# Satyrr_six_loadcell_pcb.net
KiCad netlist of a schematic drawn in EAGLE
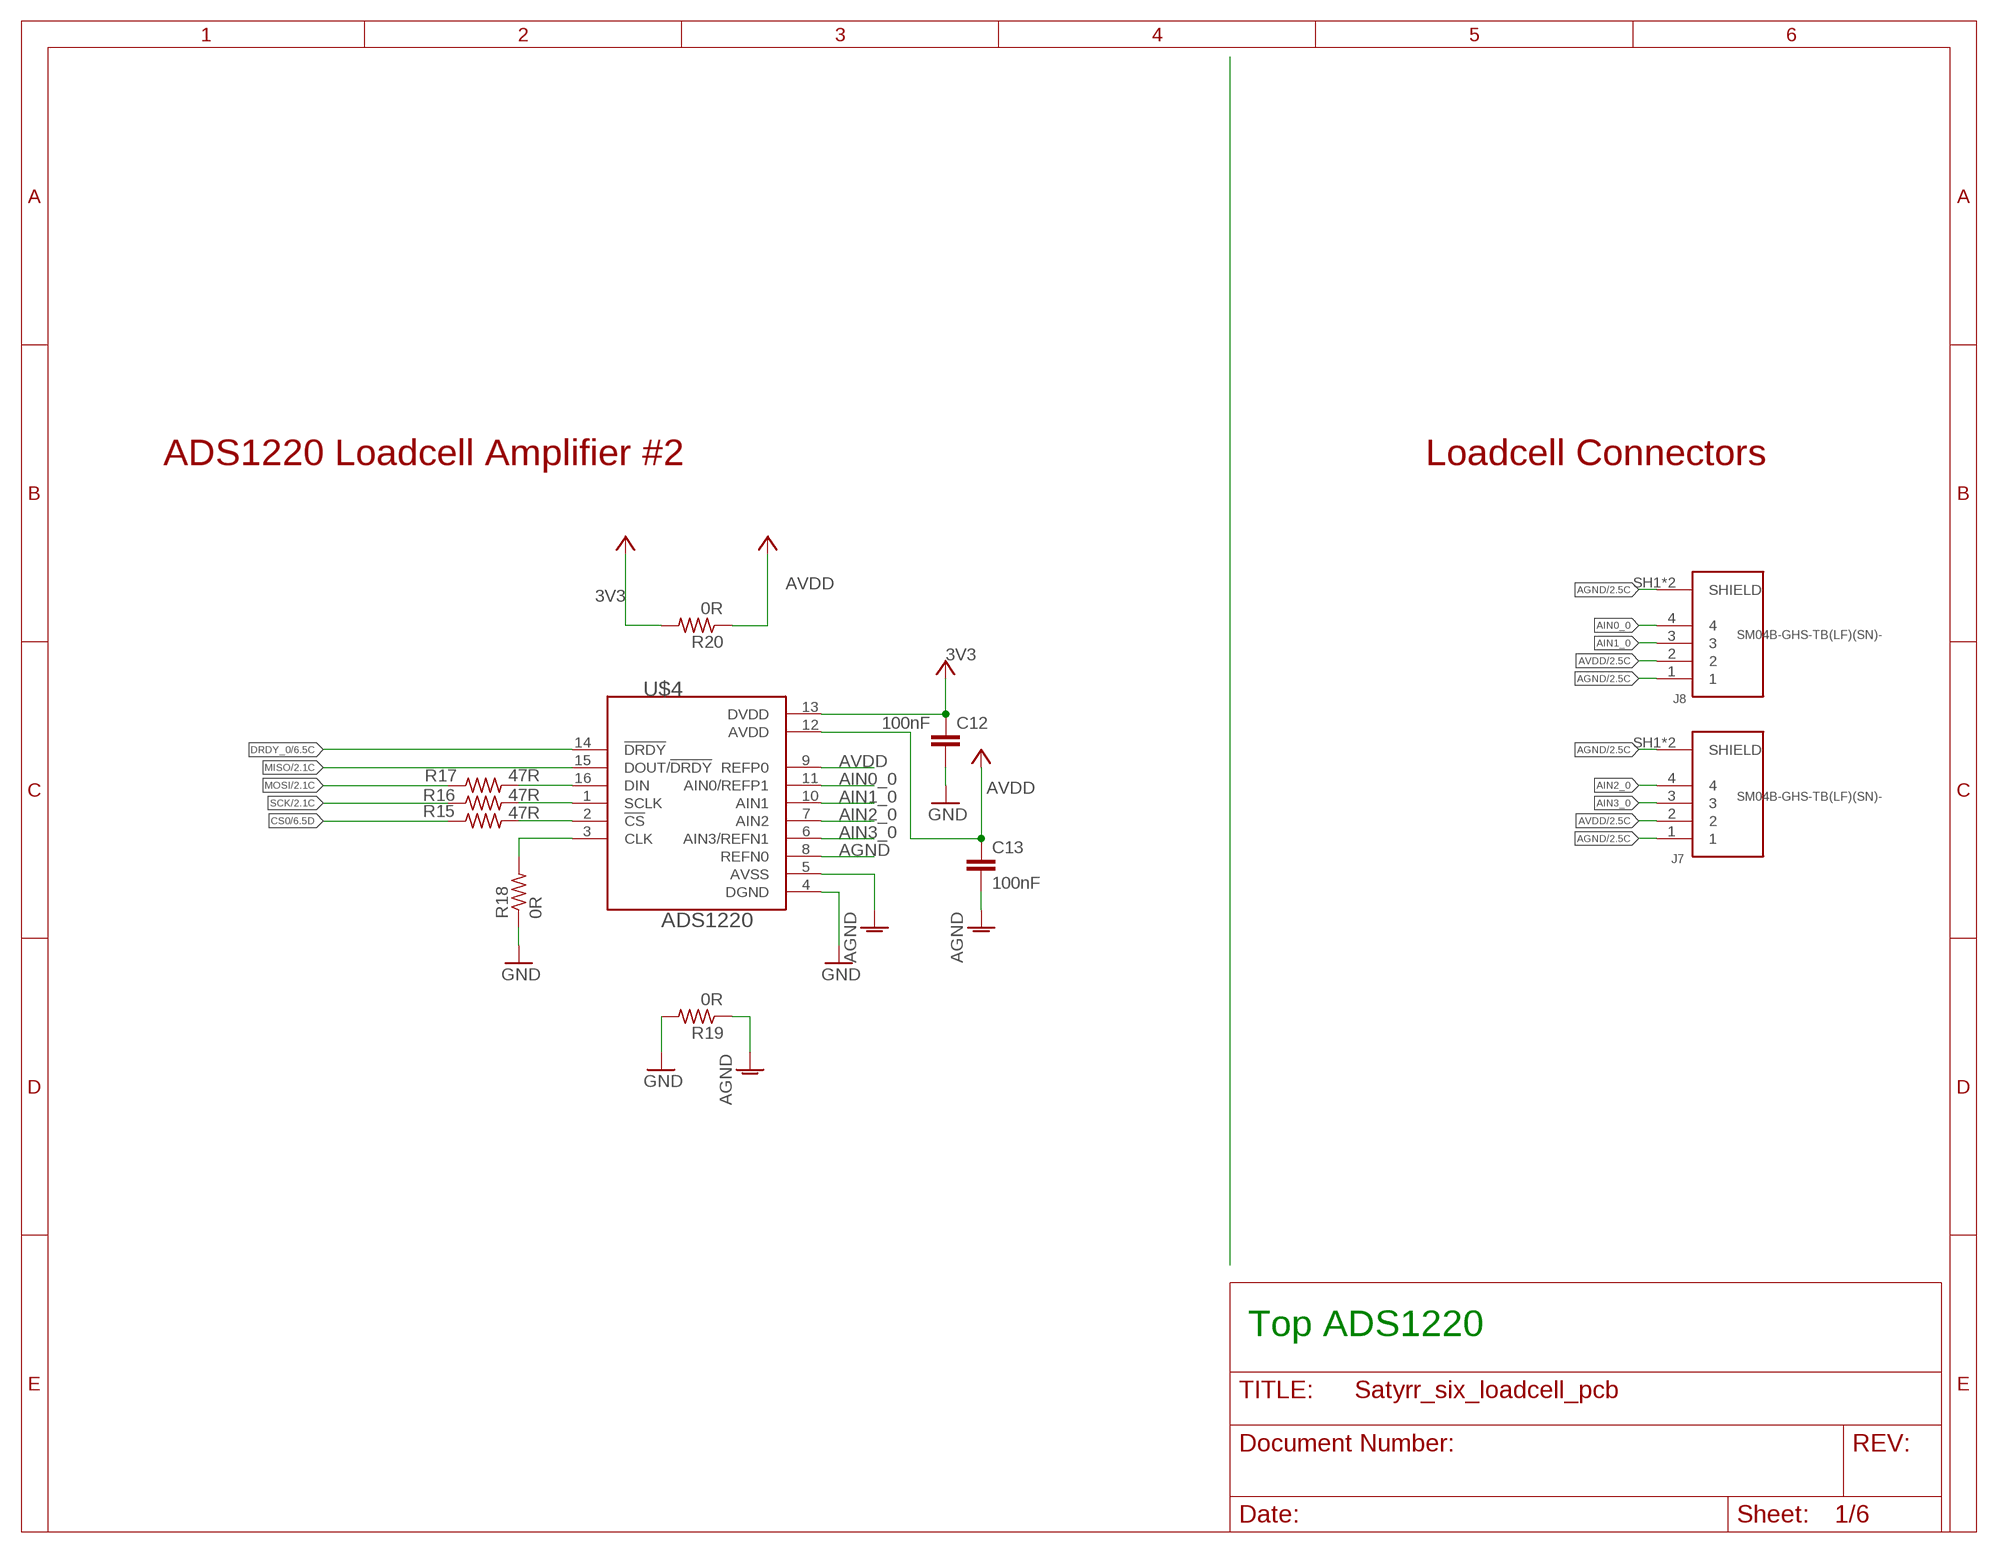
[diagram p0: schematic, sheet 1]
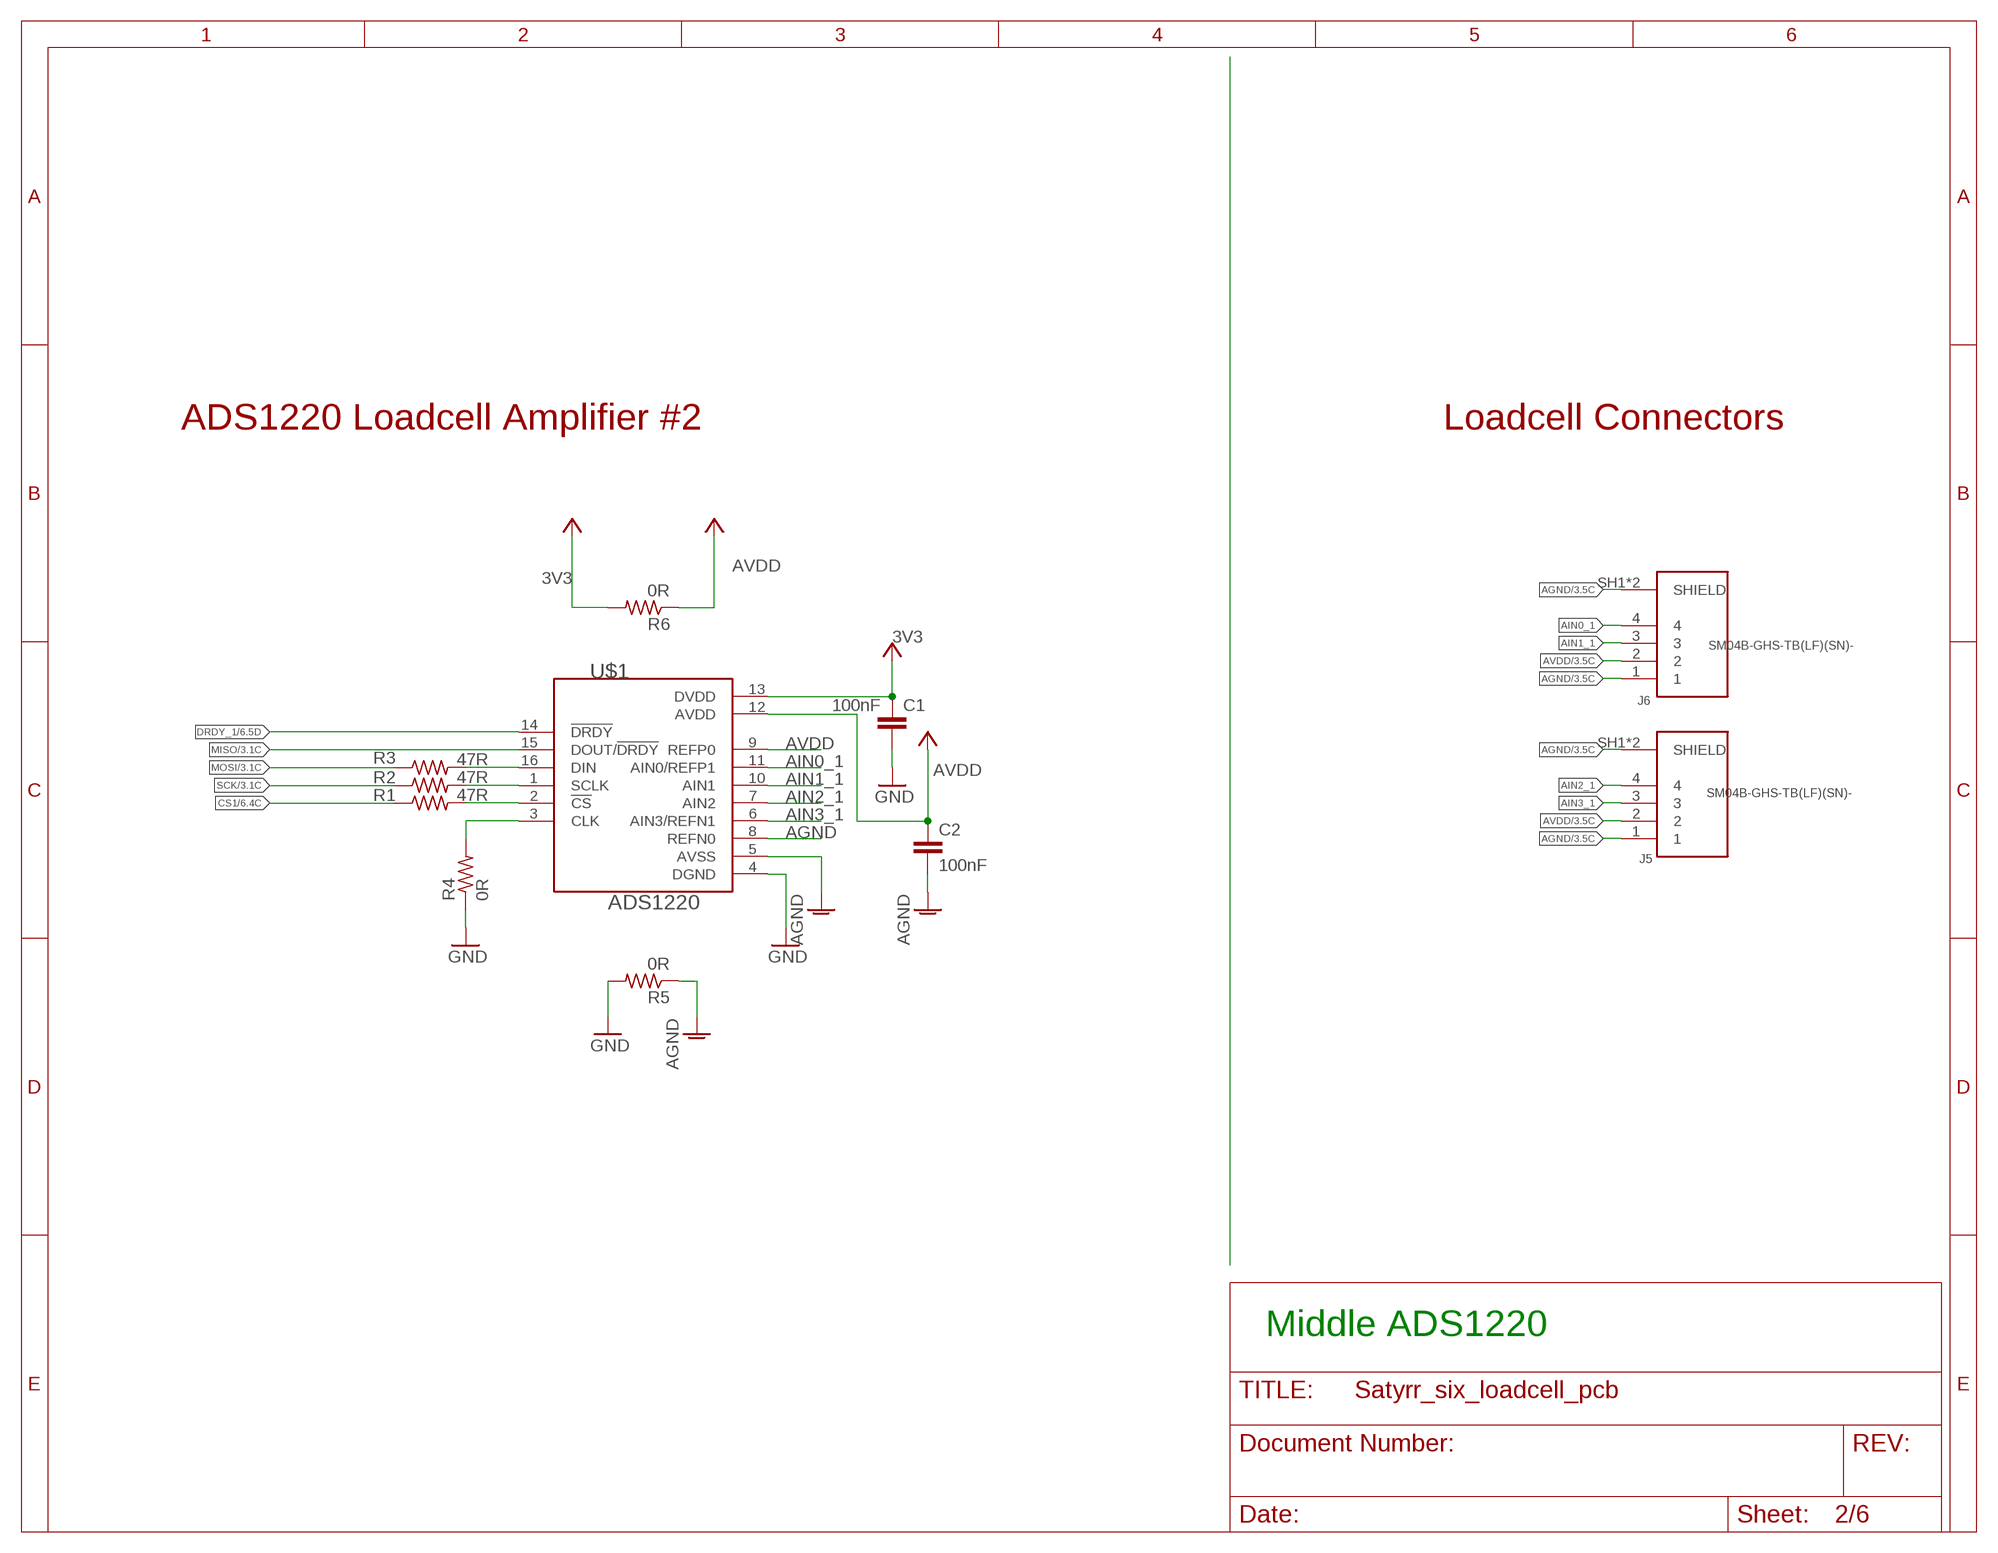
[diagram p1: schematic, sheet 2]
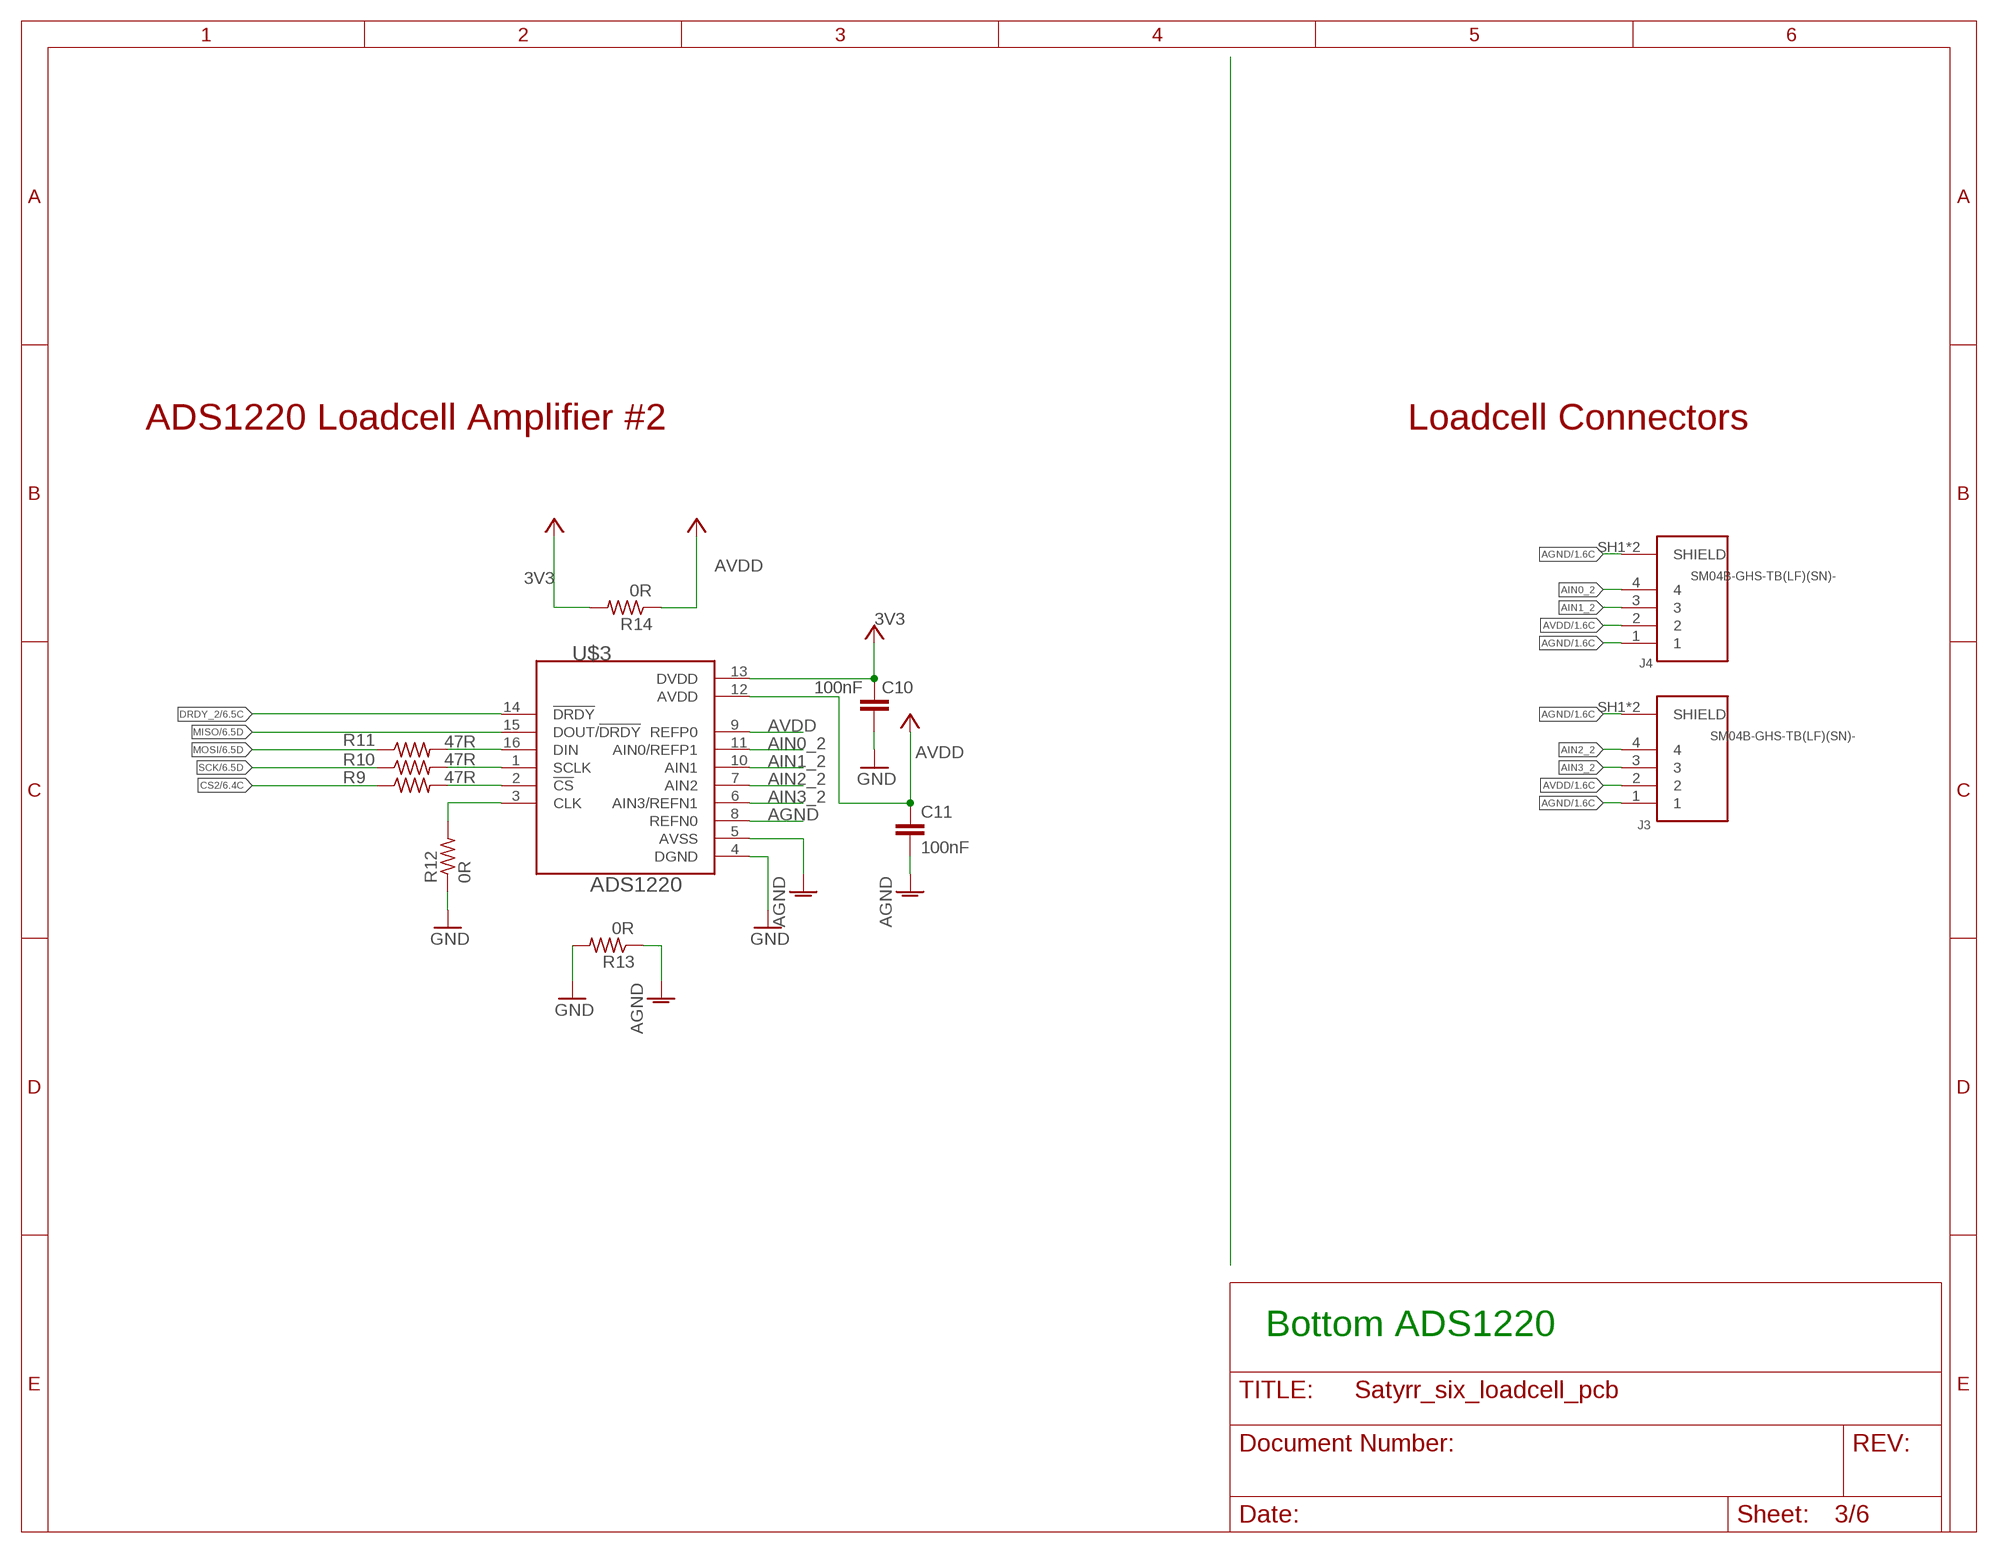
[diagram p2: schematic, sheet 3]
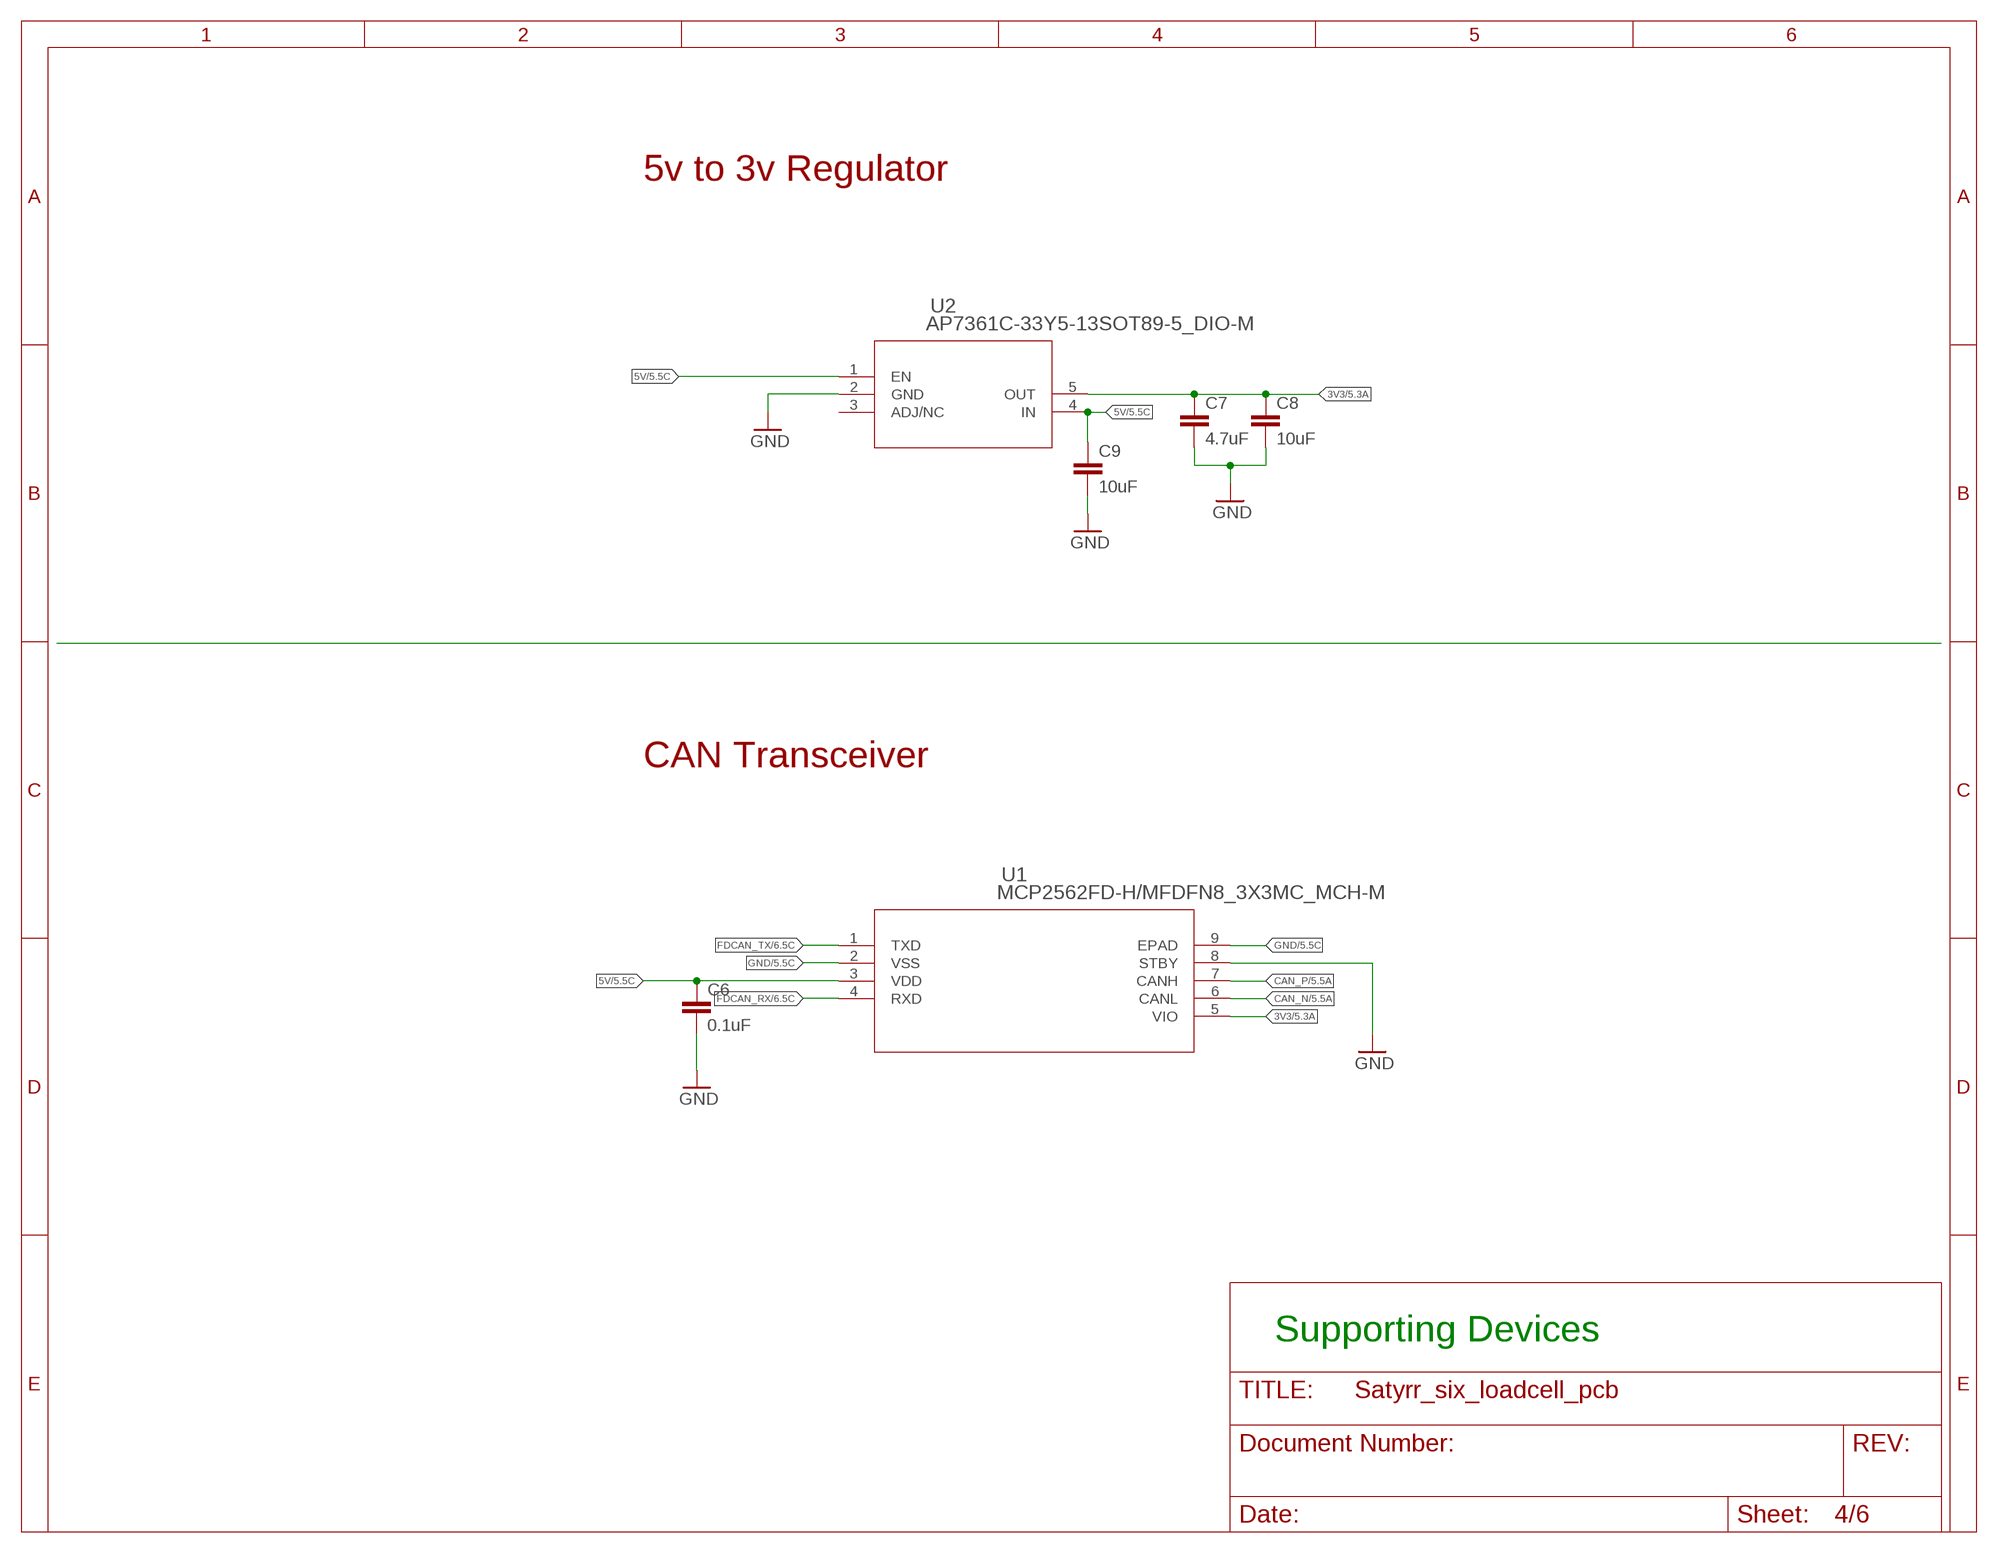
[diagram p3: schematic, sheet 4]
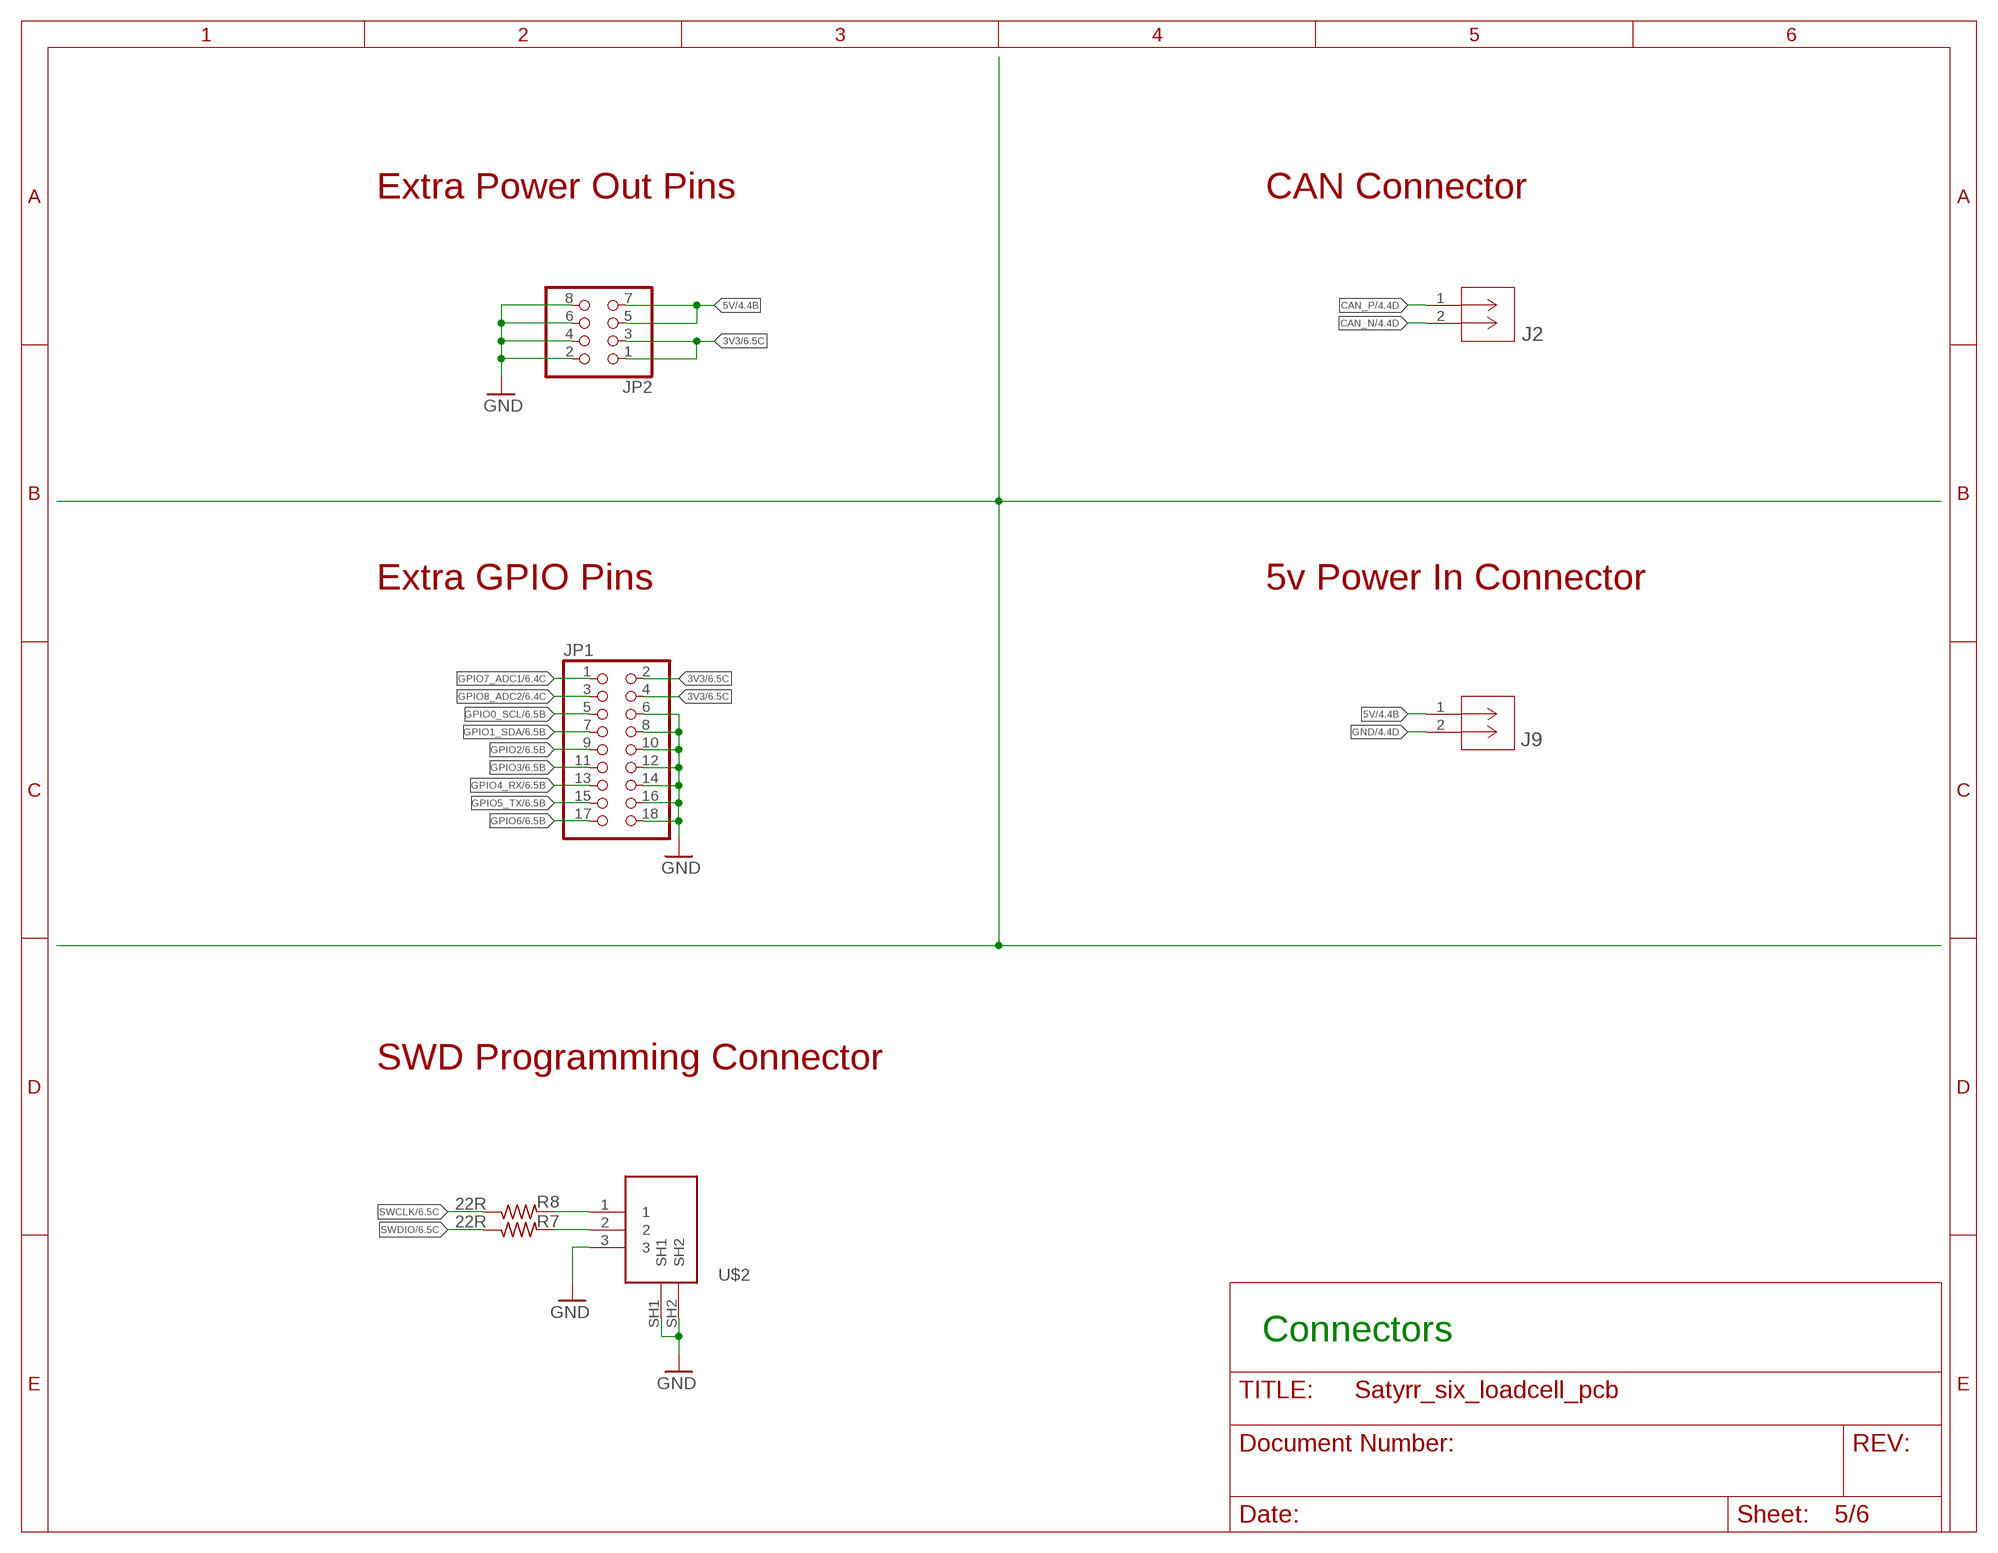
[diagram p4: schematic, sheet 5]
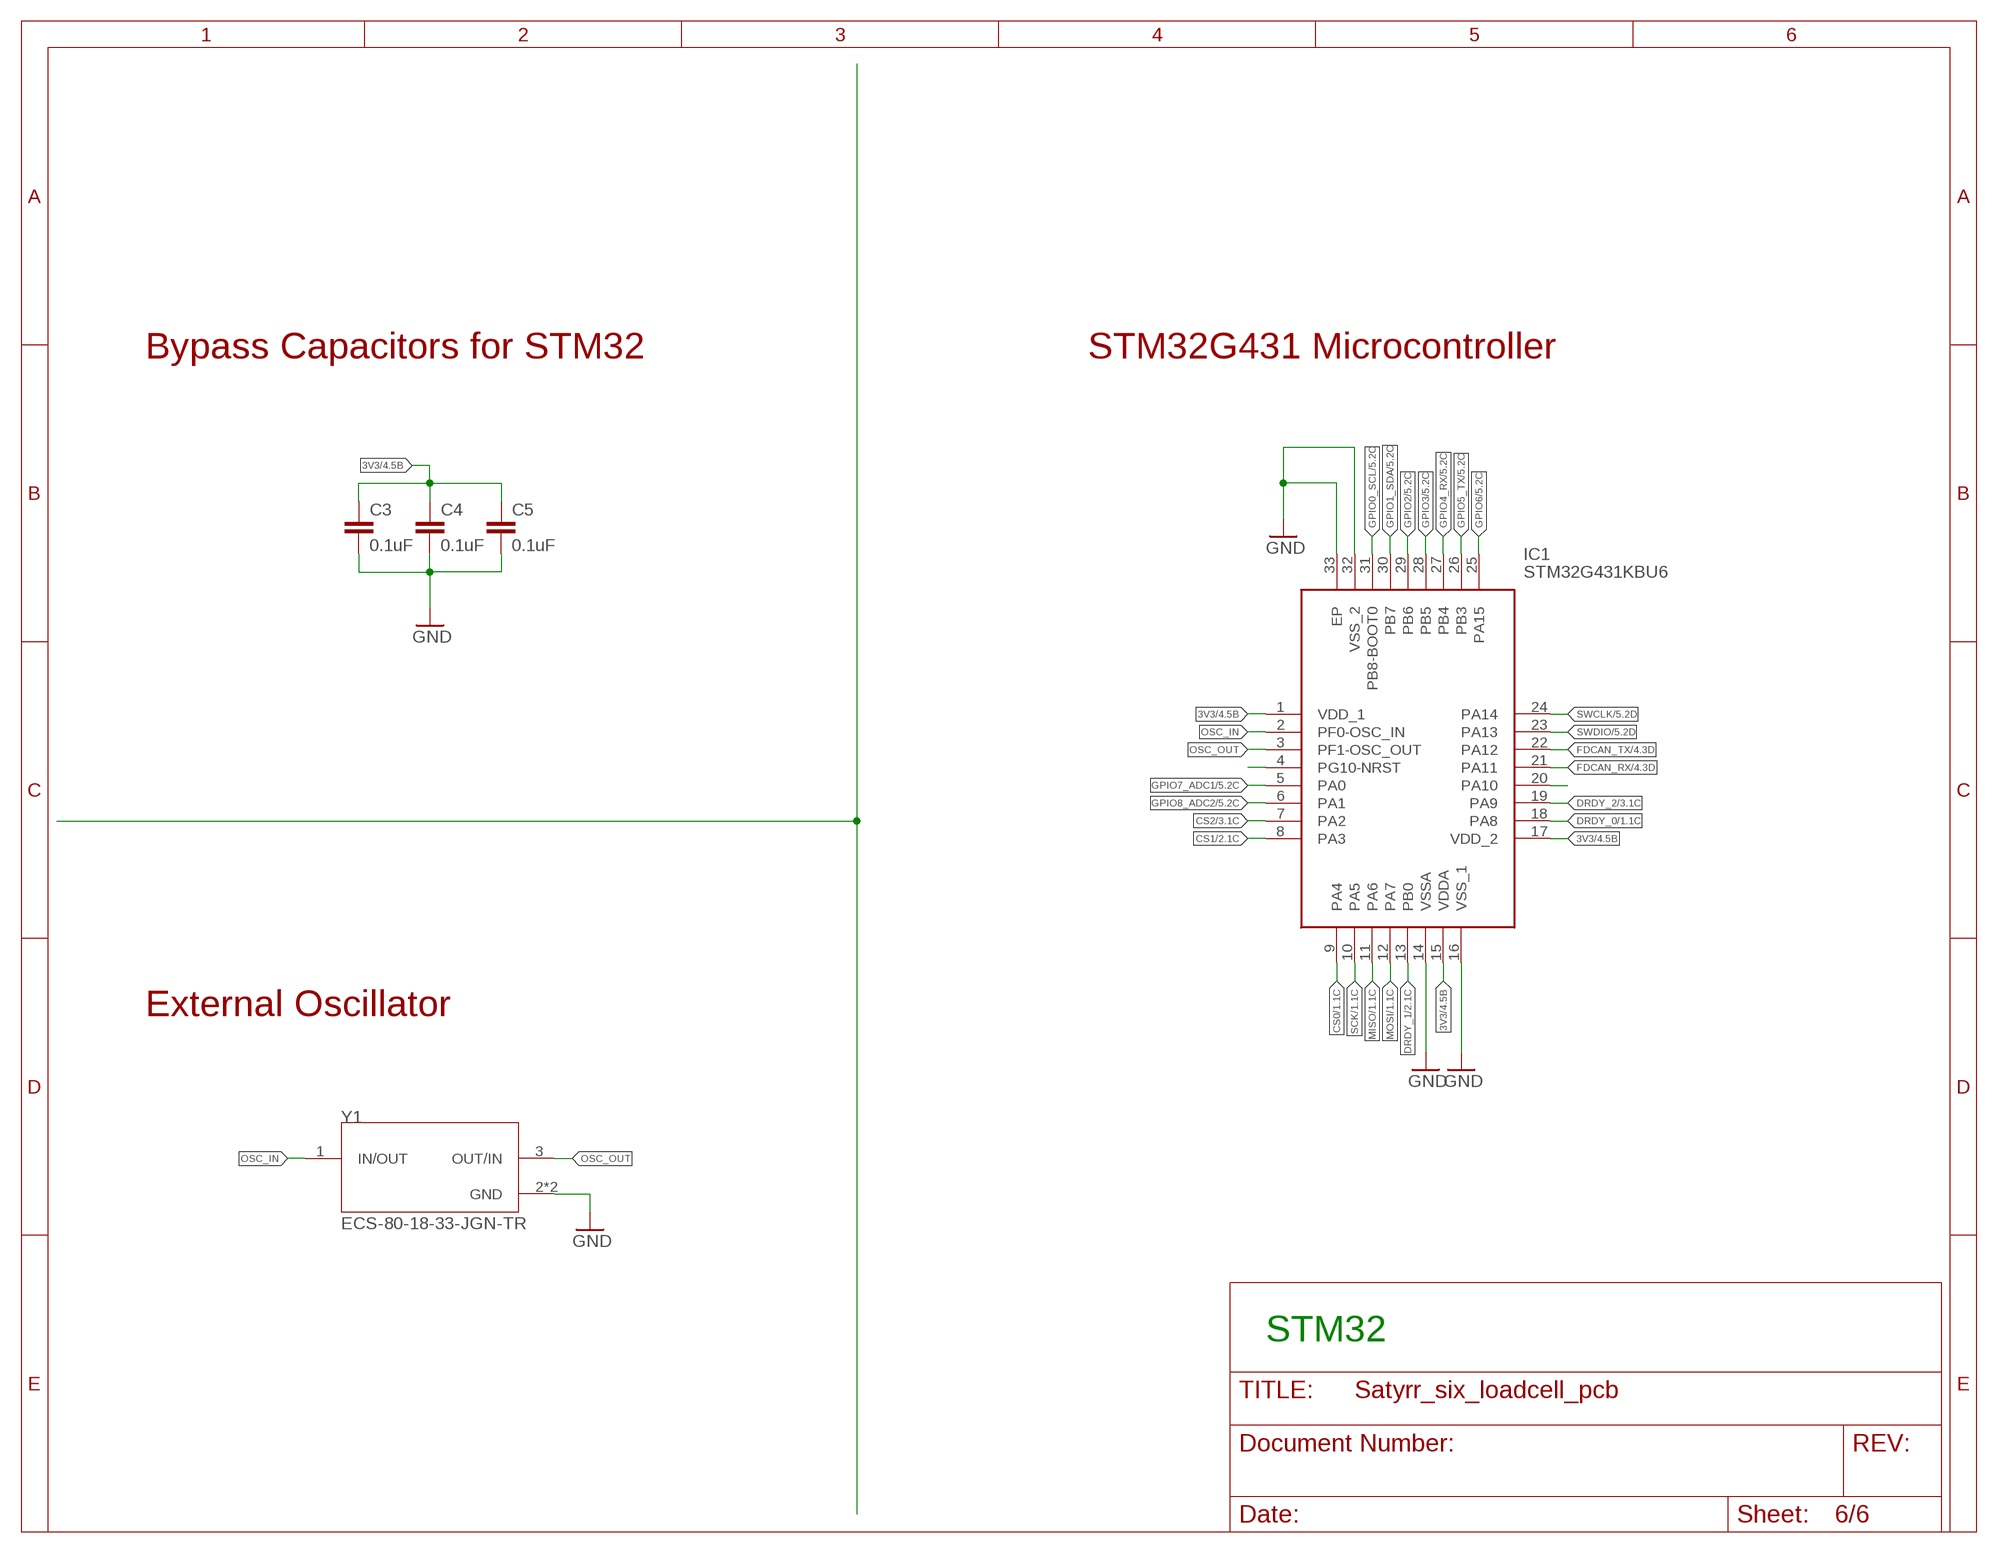
[diagram p5: schematic, sheet 6]

(export (version "E")
  (design (tool "Eeschema 10.0.6"))
  (components
    (comp (ref "J2")
      (value "SM02BGHSTBLFSN")
      (footprint "eagle-import:CONN_SM02BGHSTB_JST")
      (fields (field (name "COPYRIGHT") "Copyright (C) 2022 Ultra Librarian. All rights reserved."))
      (libsource (lib "eagle-import") (part "SM02BGHSTBLFSN"))
    )
    (comp (ref "J9")
      (value "22057025")
      (footprint "eagle-import:CON_22057025_MOL")
      (fields (field (name "COPYRIGHT") "Copyright (C) 2023 Ultra Librarian. All rights reserved."))
      (libsource (lib "eagle-import") (part "22057025"))
    )
    (comp (ref "JP1")
      (value "PINHD-2X9")
      (footprint "eagle-import:2X09")
      (libsource (lib "eagle-import") (part "PINHD-2X9"))
    )
    (comp (ref "JP2")
      (value "PINHD-2X4")
      (footprint "eagle-import:2X04")
      (libsource (lib "eagle-import") (part "PINHD-2X4"))
    )
    (comp (ref "R7")
      (value "22R")
      (footprint "eagle-import:R0603")
      (libsource (lib "eagle-import") (part "R-US_R0603"))
    )
    (comp (ref "R8")
      (value "22R")
      (footprint "eagle-import:R0603")
      (libsource (lib "eagle-import") (part "R-US_R0603"))
    )
    (comp (ref "U$2")
      (value "125SH-G-03-TR-SMT")
      (footprint "eagle-import:125SH-G-03-TR-SMT")
      (libsource (lib "eagle-import") (part "125SH-G-03-TR-SMT"))
    )
    (comp (ref "C6")
      (value "0.1uF")
      (footprint "eagle-import:C0603")
      (libsource (lib "eagle-import") (part "C-EUC0603"))
    )
    (comp (ref "C7")
      (value "4.7uF")
      (footprint "eagle-import:C0603")
      (libsource (lib "eagle-import") (part "C-EUC0603"))
    )
    (comp (ref "C8")
      (value "10uF")
      (footprint "eagle-import:C0603")
      (libsource (lib "eagle-import") (part "C-EUC0603"))
    )
    (comp (ref "C9")
      (value "10uF")
      (footprint "eagle-import:C0603")
      (libsource (lib "eagle-import") (part "C-EUC0603"))
    )
    (comp (ref "U1")
      (value "MCP2562FD-H/MFDFN8_3X3MC_MCH-M")
      (footprint "eagle-import:DFN8_3X3MC_MCH-M")
      (fields
        (field (name "MANUFACTURER_PART_NUMBER") "MCP2562FD-H/MF")
        (field (name "COPYRIGHT") "Copyright (C) 2023 Ultra Librarian. All rights reserved.")
      )
      (libsource (lib "eagle-import") (part "MCP2562FD-H/MFDFN8_3X3MC_MCH-M"))
    )
    (comp (ref "U2")
      (value "AP7361C-33Y5-13SOT89-5_DIO-M")
      (footprint "eagle-import:SOT89-5_DIO-M")
      (fields
        (field (name "MANUFACTURER_PART_NUMBER") "AP7361C-33Y5-13")
        (field (name "COPYRIGHT") "Copyright (C) 2023 Ultra Librarian. All rights reserved.")
      )
      (libsource (lib "eagle-import") (part "AP7361C-33Y5-13SOT89-5_DIO-M"))
    )
    (comp (ref "C3")
      (value "0.1uF")
      (footprint "eagle-import:C0603")
      (libsource (lib "eagle-import") (part "C-EUC0603"))
    )
    (comp (ref "C4")
      (value "0.1uF")
      (footprint "eagle-import:C0603")
      (libsource (lib "eagle-import") (part "C-EUC0603"))
    )
    (comp (ref "C5")
      (value "0.1uF")
      (footprint "eagle-import:C0603")
      (libsource (lib "eagle-import") (part "C-EUC0603"))
    )
    (comp (ref "IC1")
      (value "STM32G431KBU6")
      (footprint "eagle-import:QFN50P500X500X60-33N")
      (fields (field (name "MOUSER_PART_NUMBER") "511-STM32G431KBU6"))
      (libsource (lib "eagle-import") (part "STM32G431KBU6"))
    )
    (comp (ref "Y1")
      (value "ECS-80-18-33-JGN-TR")
      (footprint "eagle-import:XTAL_ECS-240-8-33-AGN-TR")
      (fields (field (name "MF") "ECS INC") (field (name "MP") "ECX-32"))
      (libsource (lib "eagle-import") (part "ECS-80-18-33-JGN-TR"))
    )
    (comp (ref "C10")
      (value "100nF")
      (footprint "eagle-import:C0603")
      (libsource (lib "eagle-import") (part "C-EUC0603"))
    )
    (comp (ref "C11")
      (value "100nF")
      (footprint "eagle-import:C0603")
      (libsource (lib "eagle-import") (part "C-EUC0603"))
    )
    (comp (ref "J3")
      (value "SM04B-GHS-TB(LF)(SN)-")
      (footprint "eagle-import:JST_SM04B-GHS-TB(LF)(SN)-")
      (fields (field (name "DIGI-KEY_PART_NUMBER") "455-1566-2-ND") (field (name "MF") "JST Sales"))
      (libsource (lib "eagle-import") (part "SM04B-GHS-TB(LF)(SN)-"))
    )
    (comp (ref "J4")
      (value "SM04B-GHS-TB(LF)(SN)-")
      (footprint "eagle-import:JST_SM04B-GHS-TB(LF)(SN)-")
      (fields (field (name "DIGI-KEY_PART_NUMBER") "455-1566-2-ND") (field (name "MF") "JST Sales"))
      (libsource (lib "eagle-import") (part "SM04B-GHS-TB(LF)(SN)-"))
    )
    (comp (ref "R9")
      (value "47R")
      (footprint "eagle-import:R0603")
      (libsource (lib "eagle-import") (part "R-US_R0603"))
    )
    (comp (ref "R10")
      (value "47R")
      (footprint "eagle-import:R0603")
      (libsource (lib "eagle-import") (part "R-US_R0603"))
    )
    (comp (ref "R11")
      (value "47R")
      (footprint "eagle-import:R0603")
      (libsource (lib "eagle-import") (part "R-US_R0603"))
    )
    (comp (ref "R12")
      (value "0R")
      (footprint "eagle-import:R0603")
      (libsource (lib "eagle-import") (part "R-US_R0603"))
    )
    (comp (ref "R13")
      (value "0R")
      (footprint "eagle-import:R0603")
      (libsource (lib "eagle-import") (part "R-US_R0603"))
    )
    (comp (ref "R14")
      (value "0R")
      (footprint "eagle-import:R0603")
      (libsource (lib "eagle-import") (part "R-US_R0603"))
    )
    (comp (ref "U$3")
      (value "ADS1220")
      (footprint "eagle-import:TSSOP-16")
      (libsource (lib "eagle-import") (part "ADS1220"))
    )
    (comp (ref "C12")
      (value "100nF")
      (footprint "eagle-import:C0603")
      (libsource (lib "eagle-import") (part "C-EUC0603"))
    )
    (comp (ref "C13")
      (value "100nF")
      (footprint "eagle-import:C0603")
      (libsource (lib "eagle-import") (part "C-EUC0603"))
    )
    (comp (ref "J7")
      (value "SM04B-GHS-TB(LF)(SN)-")
      (footprint "eagle-import:JST_SM04B-GHS-TB(LF)(SN)-")
      (fields (field (name "DIGI-KEY_PART_NUMBER") "455-1566-2-ND") (field (name "MF") "JST Sales"))
      (libsource (lib "eagle-import") (part "SM04B-GHS-TB(LF)(SN)-"))
    )
    (comp (ref "J8")
      (value "SM04B-GHS-TB(LF)(SN)-")
      (footprint "eagle-import:JST_SM04B-GHS-TB(LF)(SN)-")
      (fields (field (name "DIGI-KEY_PART_NUMBER") "455-1566-2-ND") (field (name "MF") "JST Sales"))
      (libsource (lib "eagle-import") (part "SM04B-GHS-TB(LF)(SN)-"))
    )
    (comp (ref "R15")
      (value "47R")
      (footprint "eagle-import:R0603")
      (libsource (lib "eagle-import") (part "R-US_R0603"))
    )
    (comp (ref "R16")
      (value "47R")
      (footprint "eagle-import:R0603")
      (libsource (lib "eagle-import") (part "R-US_R0603"))
    )
    (comp (ref "R17")
      (value "47R")
      (footprint "eagle-import:R0603")
      (libsource (lib "eagle-import") (part "R-US_R0603"))
    )
    (comp (ref "R18")
      (value "0R")
      (footprint "eagle-import:R0603")
      (libsource (lib "eagle-import") (part "R-US_R0603"))
    )
    (comp (ref "R19")
      (value "0R")
      (footprint "eagle-import:R0603")
      (libsource (lib "eagle-import") (part "R-US_R0603"))
    )
    (comp (ref "R20")
      (value "0R")
      (footprint "eagle-import:R0603")
      (libsource (lib "eagle-import") (part "R-US_R0603"))
    )
    (comp (ref "U$4")
      (value "ADS1220")
      (footprint "eagle-import:TSSOP-16")
      (libsource (lib "eagle-import") (part "ADS1220"))
    )
    (comp (ref "C1")
      (value "100nF")
      (footprint "eagle-import:C0603")
      (libsource (lib "eagle-import") (part "C-EUC0603"))
    )
    (comp (ref "C2")
      (value "100nF")
      (footprint "eagle-import:C0603")
      (libsource (lib "eagle-import") (part "C-EUC0603"))
    )
    (comp (ref "J5")
      (value "SM04B-GHS-TB(LF)(SN)-")
      (footprint "eagle-import:JST_SM04B-GHS-TB(LF)(SN)-")
      (fields (field (name "DIGI-KEY_PART_NUMBER") "455-1566-2-ND") (field (name "MF") "JST Sales"))
      (libsource (lib "eagle-import") (part "SM04B-GHS-TB(LF)(SN)-"))
    )
    (comp (ref "J6")
      (value "SM04B-GHS-TB(LF)(SN)-")
      (footprint "eagle-import:JST_SM04B-GHS-TB(LF)(SN)-")
      (fields (field (name "DIGI-KEY_PART_NUMBER") "455-1566-2-ND") (field (name "MF") "JST Sales"))
      (libsource (lib "eagle-import") (part "SM04B-GHS-TB(LF)(SN)-"))
    )
    (comp (ref "R1")
      (value "47R")
      (footprint "eagle-import:R0603")
      (libsource (lib "eagle-import") (part "R-US_R0603"))
    )
    (comp (ref "R2")
      (value "47R")
      (footprint "eagle-import:R0603")
      (libsource (lib "eagle-import") (part "R-US_R0603"))
    )
    (comp (ref "R3")
      (value "47R")
      (footprint "eagle-import:R0603")
      (libsource (lib "eagle-import") (part "R-US_R0603"))
    )
    (comp (ref "R4")
      (value "0R")
      (footprint "eagle-import:R0603")
      (libsource (lib "eagle-import") (part "R-US_R0603"))
    )
    (comp (ref "R5")
      (value "0R")
      (footprint "eagle-import:R0603")
      (libsource (lib "eagle-import") (part "R-US_R0603"))
    )
    (comp (ref "R6")
      (value "0R")
      (footprint "eagle-import:R0603")
      (libsource (lib "eagle-import") (part "R-US_R0603"))
    )
    (comp (ref "U$1")
      (value "ADS1220")
      (footprint "eagle-import:TSSOP-16")
      (libsource (lib "eagle-import") (part "ADS1220"))
    )
  )
  (nets
    (net (code "1") (name "3V3") (class "Default")
      (node (ref "C1") (pin "1") (pinfunction "1_1") (pintype "passive"))
      (node (ref "C10") (pin "1") (pinfunction "1_1") (pintype "passive"))
      (node (ref "C12") (pin "1") (pinfunction "1_1") (pintype "passive"))
      (node (ref "C3") (pin "1") (pinfunction "1_1") (pintype "passive"))
      (node (ref "C4") (pin "1") (pinfunction "1_1") (pintype "passive"))
      (node (ref "C5") (pin "1") (pinfunction "1_1") (pintype "passive"))
      (node (ref "C7") (pin "1") (pinfunction "1_1") (pintype "passive"))
      (node (ref "C8") (pin "1") (pinfunction "1_1") (pintype "passive"))
      (node (ref "IC1") (pin "1") (pinfunction "VDD_1_1") (pintype "bidirectional"))
      (node (ref "IC1") (pin "15") (pinfunction "VDDA_15") (pintype "bidirectional"))
      (node (ref "IC1") (pin "17") (pinfunction "VDD_2_17") (pintype "bidirectional"))
      (node (ref "JP1") (pin "2") (pinfunction "2_2") (pintype "passive"))
      (node (ref "JP1") (pin "4") (pinfunction "4_4") (pintype "passive"))
      (node (ref "JP2") (pin "1") (pinfunction "1_1") (pintype "passive"))
      (node (ref "JP2") (pin "3") (pinfunction "3_3") (pintype "passive"))
      (node (ref "R14") (pin "2") (pinfunction "2_2") (pintype "passive"))
      (node (ref "R20") (pin "2") (pinfunction "2_2") (pintype "passive"))
      (node (ref "R6") (pin "2") (pinfunction "2_2") (pintype "passive"))
      (node (ref "U$1") (pin "13") (pinfunction "DVDD_13") (pintype "bidirectional"))
      (node (ref "U$3") (pin "13") (pinfunction "DVDD_13") (pintype "bidirectional"))
      (node (ref "U$4") (pin "13") (pinfunction "DVDD_13") (pintype "bidirectional"))
      (node (ref "U1") (pin "5") (pinfunction "VIO_5") (pintype "passive"))
      (node (ref "U2") (pin "5") (pinfunction "OUT_5") (pintype "power_in"))
    )
    (net (code "2") (name "5V") (class "Default")
      (node (ref "C6") (pin "1") (pinfunction "1_1") (pintype "passive"))
      (node (ref "C9") (pin "1") (pinfunction "1_1") (pintype "passive"))
      (node (ref "J9") (pin "1") (pinfunction "1_1") (pintype "passive"))
      (node (ref "JP2") (pin "5") (pinfunction "5_5") (pintype "passive"))
      (node (ref "JP2") (pin "7") (pinfunction "7_7") (pintype "passive"))
      (node (ref "U1") (pin "3") (pinfunction "VDD_3") (pintype "power_in"))
      (node (ref "U2") (pin "1") (pinfunction "EN_1") (pintype "input"))
      (node (ref "U2") (pin "4") (pinfunction "IN_4") (pintype "power_in"))
    )
    (net (code "3") (name "AGND") (class "Default")
      (node (ref "C11") (pin "2") (pinfunction "2_2") (pintype "passive"))
      (node (ref "C13") (pin "2") (pinfunction "2_2") (pintype "passive"))
      (node (ref "C2") (pin "2") (pinfunction "2_2") (pintype "passive"))
      (node (ref "J3") (pin "1") (pinfunction "1_1") (pintype "passive"))
      (node (ref "J3") (pin "SH1") (pinfunction "SHIELD_SH1") (pintype "power_in"))
      (node (ref "J3") (pin "SH2") (pinfunction "SHIELD_SH2") (pintype "power_in"))
      (node (ref "J4") (pin "1") (pinfunction "1_1") (pintype "passive"))
      (node (ref "J4") (pin "SH1") (pinfunction "SHIELD_SH1") (pintype "power_in"))
      (node (ref "J4") (pin "SH2") (pinfunction "SHIELD_SH2") (pintype "power_in"))
      (node (ref "J5") (pin "1") (pinfunction "1_1") (pintype "passive"))
      (node (ref "J5") (pin "SH1") (pinfunction "SHIELD_SH1") (pintype "power_in"))
      (node (ref "J5") (pin "SH2") (pinfunction "SHIELD_SH2") (pintype "power_in"))
      (node (ref "J6") (pin "1") (pinfunction "1_1") (pintype "passive"))
      (node (ref "J6") (pin "SH1") (pinfunction "SHIELD_SH1") (pintype "power_in"))
      (node (ref "J6") (pin "SH2") (pinfunction "SHIELD_SH2") (pintype "power_in"))
      (node (ref "J7") (pin "1") (pinfunction "1_1") (pintype "passive"))
      (node (ref "J7") (pin "SH1") (pinfunction "SHIELD_SH1") (pintype "power_in"))
      (node (ref "J7") (pin "SH2") (pinfunction "SHIELD_SH2") (pintype "power_in"))
      (node (ref "J8") (pin "1") (pinfunction "1_1") (pintype "passive"))
      (node (ref "J8") (pin "SH1") (pinfunction "SHIELD_SH1") (pintype "power_in"))
      (node (ref "J8") (pin "SH2") (pinfunction "SHIELD_SH2") (pintype "power_in"))
      (node (ref "R13") (pin "1") (pinfunction "1_1") (pintype "passive"))
      (node (ref "R19") (pin "1") (pinfunction "1_1") (pintype "passive"))
      (node (ref "R5") (pin "1") (pinfunction "1_1") (pintype "passive"))
      (node (ref "U$1") (pin "5") (pinfunction "AVSS_5") (pintype "bidirectional"))
      (node (ref "U$1") (pin "8") (pinfunction "REFN0_8") (pintype "bidirectional"))
      (node (ref "U$3") (pin "5") (pinfunction "AVSS_5") (pintype "bidirectional"))
      (node (ref "U$3") (pin "8") (pinfunction "REFN0_8") (pintype "bidirectional"))
      (node (ref "U$4") (pin "5") (pinfunction "AVSS_5") (pintype "bidirectional"))
      (node (ref "U$4") (pin "8") (pinfunction "REFN0_8") (pintype "bidirectional"))
    )
    (net (code "4") (name "AIN0_0") (class "Default")
      (node (ref "J8") (pin "4") (pinfunction "4_4") (pintype "passive"))
      (node (ref "U$4") (pin "11") (pinfunction "AIN0/REFP1_11") (pintype "bidirectional"))
    )
    (net (code "5") (name "AIN0_1") (class "Default")
      (node (ref "J6") (pin "4") (pinfunction "4_4") (pintype "passive"))
      (node (ref "U$1") (pin "11") (pinfunction "AIN0/REFP1_11") (pintype "bidirectional"))
    )
    (net (code "6") (name "AIN0_2") (class "Default")
      (node (ref "J4") (pin "4") (pinfunction "4_4") (pintype "passive"))
      (node (ref "U$3") (pin "11") (pinfunction "AIN0/REFP1_11") (pintype "bidirectional"))
    )
    (net (code "7") (name "AIN1_0") (class "Default")
      (node (ref "J8") (pin "3") (pinfunction "3_3") (pintype "passive"))
      (node (ref "U$4") (pin "10") (pinfunction "AIN1_10") (pintype "bidirectional"))
    )
    (net (code "8") (name "AIN1_1") (class "Default")
      (node (ref "J6") (pin "3") (pinfunction "3_3") (pintype "passive"))
      (node (ref "U$1") (pin "10") (pinfunction "AIN1_10") (pintype "bidirectional"))
    )
    (net (code "9") (name "AIN1_2") (class "Default")
      (node (ref "J4") (pin "3") (pinfunction "3_3") (pintype "passive"))
      (node (ref "U$3") (pin "10") (pinfunction "AIN1_10") (pintype "bidirectional"))
    )
    (net (code "10") (name "AIN2_0") (class "Default")
      (node (ref "J7") (pin "4") (pinfunction "4_4") (pintype "passive"))
      (node (ref "U$4") (pin "7") (pinfunction "AIN2_7") (pintype "bidirectional"))
    )
    (net (code "11") (name "AIN2_1") (class "Default")
      (node (ref "J5") (pin "4") (pinfunction "4_4") (pintype "passive"))
      (node (ref "U$1") (pin "7") (pinfunction "AIN2_7") (pintype "bidirectional"))
    )
    (net (code "12") (name "AIN2_2") (class "Default")
      (node (ref "J3") (pin "4") (pinfunction "4_4") (pintype "passive"))
      (node (ref "U$3") (pin "7") (pinfunction "AIN2_7") (pintype "bidirectional"))
    )
    (net (code "13") (name "AIN3_0") (class "Default")
      (node (ref "J7") (pin "3") (pinfunction "3_3") (pintype "passive"))
      (node (ref "U$4") (pin "6") (pinfunction "AIN3/REFN1_6") (pintype "bidirectional"))
    )
    (net (code "14") (name "AIN3_1") (class "Default")
      (node (ref "J5") (pin "3") (pinfunction "3_3") (pintype "passive"))
      (node (ref "U$1") (pin "6") (pinfunction "AIN3/REFN1_6") (pintype "bidirectional"))
    )
    (net (code "15") (name "AIN3_2") (class "Default")
      (node (ref "J3") (pin "3") (pinfunction "3_3") (pintype "passive"))
      (node (ref "U$3") (pin "6") (pinfunction "AIN3/REFN1_6") (pintype "bidirectional"))
    )
    (net (code "16") (name "AVDD") (class "Default")
      (node (ref "C11") (pin "1") (pinfunction "1_1") (pintype "passive"))
      (node (ref "C13") (pin "1") (pinfunction "1_1") (pintype "passive"))
      (node (ref "C2") (pin "1") (pinfunction "1_1") (pintype "passive"))
      (node (ref "J3") (pin "2") (pinfunction "2_2") (pintype "passive"))
      (node (ref "J4") (pin "2") (pinfunction "2_2") (pintype "passive"))
      (node (ref "J5") (pin "2") (pinfunction "2_2") (pintype "passive"))
      (node (ref "J6") (pin "2") (pinfunction "2_2") (pintype "passive"))
      (node (ref "J7") (pin "2") (pinfunction "2_2") (pintype "passive"))
      (node (ref "J8") (pin "2") (pinfunction "2_2") (pintype "passive"))
      (node (ref "R14") (pin "1") (pinfunction "1_1") (pintype "passive"))
      (node (ref "R20") (pin "1") (pinfunction "1_1") (pintype "passive"))
      (node (ref "R6") (pin "1") (pinfunction "1_1") (pintype "passive"))
      (node (ref "U$1") (pin "12") (pinfunction "AVDD_12") (pintype "bidirectional"))
      (node (ref "U$1") (pin "9") (pinfunction "REFP0_9") (pintype "bidirectional"))
      (node (ref "U$3") (pin "12") (pinfunction "AVDD_12") (pintype "bidirectional"))
      (node (ref "U$3") (pin "9") (pinfunction "REFP0_9") (pintype "bidirectional"))
      (node (ref "U$4") (pin "12") (pinfunction "AVDD_12") (pintype "bidirectional"))
      (node (ref "U$4") (pin "9") (pinfunction "REFP0_9") (pintype "bidirectional"))
    )
    (net (code "17") (name "CAN_N") (class "Default")
      (node (ref "J2") (pin "2") (pinfunction "2_2") (pintype "passive"))
      (node (ref "U1") (pin "6") (pinfunction "CANL_6") (pintype "bidirectional"))
    )
    (net (code "18") (name "CAN_P") (class "Default")
      (node (ref "J2") (pin "1") (pinfunction "1_1") (pintype "passive"))
      (node (ref "U1") (pin "7") (pinfunction "CANH_7") (pintype "bidirectional"))
    )
    (net (code "19") (name "CS0") (class "Default")
      (node (ref "IC1") (pin "9") (pinfunction "PA4_9") (pintype "bidirectional"))
      (node (ref "R15") (pin "1") (pinfunction "1_1") (pintype "passive"))
    )
    (net (code "20") (name "CS1") (class "Default")
      (node (ref "IC1") (pin "8") (pinfunction "PA3_8") (pintype "bidirectional"))
      (node (ref "R1") (pin "1") (pinfunction "1_1") (pintype "passive"))
    )
    (net (code "21") (name "CS2") (class "Default")
      (node (ref "IC1") (pin "7") (pinfunction "PA2_7") (pintype "bidirectional"))
      (node (ref "R9") (pin "1") (pinfunction "1_1") (pintype "passive"))
    )
    (net (code "22") (name "DRDY_0") (class "Default")
      (node (ref "IC1") (pin "18") (pinfunction "PA8_18") (pintype "bidirectional"))
      (node (ref "U$4") (pin "14") (pinfunction "~{DRDY}_14") (pintype "bidirectional"))
    )
    (net (code "23") (name "DRDY_1") (class "Default")
      (node (ref "IC1") (pin "13") (pinfunction "PB0_13") (pintype "bidirectional"))
      (node (ref "U$1") (pin "14") (pinfunction "~{DRDY}_14") (pintype "bidirectional"))
    )
    (net (code "24") (name "DRDY_2") (class "Default")
      (node (ref "IC1") (pin "19") (pinfunction "PA9_19") (pintype "bidirectional"))
      (node (ref "U$3") (pin "14") (pinfunction "~{DRDY}_14") (pintype "bidirectional"))
    )
    (net (code "25") (name "FDCAN_RX") (class "Default")
      (node (ref "IC1") (pin "21") (pinfunction "PA11_21") (pintype "bidirectional"))
      (node (ref "U1") (pin "4") (pinfunction "RXD_4") (pintype "output"))
    )
    (net (code "26") (name "FDCAN_TX") (class "Default")
      (node (ref "IC1") (pin "22") (pinfunction "PA12_22") (pintype "bidirectional"))
      (node (ref "U1") (pin "1") (pinfunction "TXD_1") (pintype "input"))
    )
    (net (code "27") (name "GND") (class "Default")
      (node (ref "C1") (pin "2") (pinfunction "2_2") (pintype "passive"))
      (node (ref "C10") (pin "2") (pinfunction "2_2") (pintype "passive"))
      (node (ref "C12") (pin "2") (pinfunction "2_2") (pintype "passive"))
      (node (ref "C3") (pin "2") (pinfunction "2_2") (pintype "passive"))
      (node (ref "C4") (pin "2") (pinfunction "2_2") (pintype "passive"))
      (node (ref "C5") (pin "2") (pinfunction "2_2") (pintype "passive"))
      (node (ref "C6") (pin "2") (pinfunction "2_2") (pintype "passive"))
      (node (ref "C7") (pin "2") (pinfunction "2_2") (pintype "passive"))
      (node (ref "C8") (pin "2") (pinfunction "2_2") (pintype "passive"))
      (node (ref "C9") (pin "2") (pinfunction "2_2") (pintype "passive"))
      (node (ref "IC1") (pin "14") (pinfunction "VSSA_14") (pintype "bidirectional"))
      (node (ref "IC1") (pin "16") (pinfunction "VSS_1_16") (pintype "bidirectional"))
      (node (ref "IC1") (pin "32") (pinfunction "VSS_2_32") (pintype "bidirectional"))
      (node (ref "IC1") (pin "33") (pinfunction "EP_33") (pintype "bidirectional"))
      (node (ref "J9") (pin "2") (pinfunction "2_2") (pintype "passive"))
      (node (ref "JP1") (pin "10") (pinfunction "10_10") (pintype "passive"))
      (node (ref "JP1") (pin "12") (pinfunction "12_12") (pintype "passive"))
      (node (ref "JP1") (pin "14") (pinfunction "14_14") (pintype "passive"))
      (node (ref "JP1") (pin "16") (pinfunction "16_16") (pintype "passive"))
      (node (ref "JP1") (pin "18") (pinfunction "18_18") (pintype "passive"))
      (node (ref "JP1") (pin "6") (pinfunction "6_6") (pintype "passive"))
      (node (ref "JP1") (pin "8") (pinfunction "8_8") (pintype "passive"))
      (node (ref "JP2") (pin "2") (pinfunction "2_2") (pintype "passive"))
      (node (ref "JP2") (pin "4") (pinfunction "4_4") (pintype "passive"))
      (node (ref "JP2") (pin "6") (pinfunction "6_6") (pintype "passive"))
      (node (ref "JP2") (pin "8") (pinfunction "8_8") (pintype "passive"))
      (node (ref "R12") (pin "1") (pinfunction "1_1") (pintype "passive"))
      (node (ref "R13") (pin "2") (pinfunction "2_2") (pintype "passive"))
      (node (ref "R18") (pin "1") (pinfunction "1_1") (pintype "passive"))
      (node (ref "R19") (pin "2") (pinfunction "2_2") (pintype "passive"))
      (node (ref "R4") (pin "1") (pinfunction "1_1") (pintype "passive"))
      (node (ref "R5") (pin "2") (pinfunction "2_2") (pintype "passive"))
      (node (ref "U$1") (pin "4") (pinfunction "DGND_4") (pintype "bidirectional"))
      (node (ref "U$2") (pin "3") (pinfunction "3_3") (pintype "bidirectional"))
      (node (ref "U$2") (pin "SH1") (pinfunction "SH1_SH1") (pintype "bidirectional"))
      (node (ref "U$2") (pin "SH2") (pinfunction "SH2_SH2") (pintype "bidirectional"))
      (node (ref "U$3") (pin "4") (pinfunction "DGND_4") (pintype "bidirectional"))
      (node (ref "U$4") (pin "4") (pinfunction "DGND_4") (pintype "bidirectional"))
      (node (ref "U1") (pin "2") (pinfunction "VSS_2") (pintype "power_in"))
      (node (ref "U1") (pin "8") (pinfunction "STBY_8") (pintype "input"))
      (node (ref "U1") (pin "9") (pinfunction "EPAD_9") (pintype "passive"))
      (node (ref "U2") (pin "2") (pinfunction "GND_2") (pintype "passive"))
      (node (ref "Y1") (pin "2") (pinfunction "GND_2") (pintype "power_in"))
      (node (ref "Y1") (pin "4") (pinfunction "GND_4") (pintype "power_in"))
    )
    (net (code "28") (name "GPIO0_SCL") (class "Default")
      (node (ref "IC1") (pin "31") (pinfunction "PB8-BOOT0_31") (pintype "bidirectional"))
      (node (ref "JP1") (pin "5") (pinfunction "5_5") (pintype "passive"))
    )
    (net (code "29") (name "GPIO1_SDA") (class "Default")
      (node (ref "IC1") (pin "30") (pinfunction "PB7_30") (pintype "bidirectional"))
      (node (ref "JP1") (pin "7") (pinfunction "7_7") (pintype "passive"))
    )
    (net (code "30") (name "GPIO2") (class "Default")
      (node (ref "IC1") (pin "29") (pinfunction "PB6_29") (pintype "bidirectional"))
      (node (ref "JP1") (pin "9") (pinfunction "9_9") (pintype "passive"))
    )
    (net (code "31") (name "GPIO3") (class "Default")
      (node (ref "IC1") (pin "28") (pinfunction "PB5_28") (pintype "bidirectional"))
      (node (ref "JP1") (pin "11") (pinfunction "11_11") (pintype "passive"))
    )
    (net (code "32") (name "GPIO4_RX") (class "Default")
      (node (ref "IC1") (pin "27") (pinfunction "PB4_27") (pintype "bidirectional"))
      (node (ref "JP1") (pin "13") (pinfunction "13_13") (pintype "passive"))
    )
    (net (code "33") (name "GPIO5_TX") (class "Default")
      (node (ref "IC1") (pin "26") (pinfunction "PB3_26") (pintype "bidirectional"))
      (node (ref "JP1") (pin "15") (pinfunction "15_15") (pintype "passive"))
    )
    (net (code "34") (name "GPIO6") (class "Default")
      (node (ref "IC1") (pin "25") (pinfunction "PA15_25") (pintype "bidirectional"))
      (node (ref "JP1") (pin "17") (pinfunction "17_17") (pintype "passive"))
    )
    (net (code "35") (name "GPIO7_ADC1") (class "Default")
      (node (ref "IC1") (pin "5") (pinfunction "PA0_5") (pintype "bidirectional"))
      (node (ref "JP1") (pin "1") (pinfunction "1_1") (pintype "passive"))
    )
    (net (code "36") (name "GPIO8_ADC2") (class "Default")
      (node (ref "IC1") (pin "6") (pinfunction "PA1_6") (pintype "bidirectional"))
      (node (ref "JP1") (pin "3") (pinfunction "3_3") (pintype "passive"))
    )
    (net (code "37") (name "MISO") (class "Default")
      (node (ref "IC1") (pin "11") (pinfunction "PA6_11") (pintype "bidirectional"))
      (node (ref "U$1") (pin "15") (pinfunction "DOUT/~{DRDY}_15") (pintype "bidirectional"))
      (node (ref "U$3") (pin "15") (pinfunction "DOUT/~{DRDY}_15") (pintype "bidirectional"))
      (node (ref "U$4") (pin "15") (pinfunction "DOUT/~{DRDY}_15") (pintype "bidirectional"))
    )
    (net (code "38") (name "MOSI") (class "Default")
      (node (ref "IC1") (pin "12") (pinfunction "PA7_12") (pintype "bidirectional"))
      (node (ref "R11") (pin "1") (pinfunction "1_1") (pintype "passive"))
      (node (ref "R17") (pin "1") (pinfunction "1_1") (pintype "passive"))
      (node (ref "R3") (pin "1") (pinfunction "1_1") (pintype "passive"))
    )
    (net (code "39") (name "Net-(R7-Pad2)") (class "Default")
      (node (ref "R7") (pin "2") (pinfunction "2_2") (pintype "passive"))
      (node (ref "U$2") (pin "2") (pinfunction "2_2") (pintype "bidirectional"))
    )
    (net (code "40") (name "Net-(R8-Pad2)") (class "Default")
      (node (ref "R8") (pin "2") (pinfunction "2_2") (pintype "passive"))
      (node (ref "U$2") (pin "1") (pinfunction "1_1") (pintype "bidirectional"))
    )
    (net (code "41") (name "Net-(U$1-CLK)") (class "Default")
      (node (ref "R4") (pin "2") (pinfunction "2_2") (pintype "passive"))
      (node (ref "U$1") (pin "3") (pinfunction "CLK_3") (pintype "bidirectional"))
    )
    (net (code "42") (name "Net-(U$1-DIN)") (class "Default")
      (node (ref "R3") (pin "2") (pinfunction "2_2") (pintype "passive"))
      (node (ref "U$1") (pin "16") (pinfunction "DIN_16") (pintype "bidirectional"))
    )
    (net (code "43") (name "Net-(U$1-SCLK)") (class "Default")
      (node (ref "R2") (pin "2") (pinfunction "2_2") (pintype "passive"))
      (node (ref "U$1") (pin "1") (pinfunction "SCLK_1") (pintype "bidirectional"))
    )
    (net (code "44") (name "Net-(U$1-~{CS})") (class "Default")
      (node (ref "R1") (pin "2") (pinfunction "2_2") (pintype "passive"))
      (node (ref "U$1") (pin "2") (pinfunction "~{CS}_2") (pintype "bidirectional"))
    )
    (net (code "45") (name "Net-(U$3-CLK)") (class "Default")
      (node (ref "R12") (pin "2") (pinfunction "2_2") (pintype "passive"))
      (node (ref "U$3") (pin "3") (pinfunction "CLK_3") (pintype "bidirectional"))
    )
    (net (code "46") (name "Net-(U$3-DIN)") (class "Default")
      (node (ref "R11") (pin "2") (pinfunction "2_2") (pintype "passive"))
      (node (ref "U$3") (pin "16") (pinfunction "DIN_16") (pintype "bidirectional"))
    )
    (net (code "47") (name "Net-(U$3-SCLK)") (class "Default")
      (node (ref "R10") (pin "2") (pinfunction "2_2") (pintype "passive"))
      (node (ref "U$3") (pin "1") (pinfunction "SCLK_1") (pintype "bidirectional"))
    )
    (net (code "48") (name "Net-(U$3-~{CS})") (class "Default")
      (node (ref "R9") (pin "2") (pinfunction "2_2") (pintype "passive"))
      (node (ref "U$3") (pin "2") (pinfunction "~{CS}_2") (pintype "bidirectional"))
    )
    (net (code "49") (name "Net-(U$4-CLK)") (class "Default")
      (node (ref "R18") (pin "2") (pinfunction "2_2") (pintype "passive"))
      (node (ref "U$4") (pin "3") (pinfunction "CLK_3") (pintype "bidirectional"))
    )
    (net (code "50") (name "Net-(U$4-DIN)") (class "Default")
      (node (ref "R17") (pin "2") (pinfunction "2_2") (pintype "passive"))
      (node (ref "U$4") (pin "16") (pinfunction "DIN_16") (pintype "bidirectional"))
    )
    (net (code "51") (name "Net-(U$4-SCLK)") (class "Default")
      (node (ref "R16") (pin "2") (pinfunction "2_2") (pintype "passive"))
      (node (ref "U$4") (pin "1") (pinfunction "SCLK_1") (pintype "bidirectional"))
    )
    (net (code "52") (name "Net-(U$4-~{CS})") (class "Default")
      (node (ref "R15") (pin "2") (pinfunction "2_2") (pintype "passive"))
      (node (ref "U$4") (pin "2") (pinfunction "~{CS}_2") (pintype "bidirectional"))
    )
    (net (code "53") (name "OSC_IN") (class "Default")
      (node (ref "IC1") (pin "2") (pinfunction "PF0-OSC_IN_2") (pintype "bidirectional"))
      (node (ref "Y1") (pin "1") (pinfunction "IN/OUT_1") (pintype "bidirectional"))
    )
    (net (code "54") (name "OSC_OUT") (class "Default")
      (node (ref "IC1") (pin "3") (pinfunction "PF1-OSC_OUT_3") (pintype "bidirectional"))
      (node (ref "Y1") (pin "3") (pinfunction "OUT/IN_3") (pintype "bidirectional"))
    )
    (net (code "55") (name "SCK") (class "Default")
      (node (ref "IC1") (pin "10") (pinfunction "PA5_10") (pintype "bidirectional"))
      (node (ref "R10") (pin "1") (pinfunction "1_1") (pintype "passive"))
      (node (ref "R16") (pin "1") (pinfunction "1_1") (pintype "passive"))
      (node (ref "R2") (pin "1") (pinfunction "1_1") (pintype "passive"))
    )
    (net (code "56") (name "SWCLK") (class "Default")
      (node (ref "IC1") (pin "24") (pinfunction "PA14_24") (pintype "bidirectional"))
      (node (ref "R8") (pin "1") (pinfunction "1_1") (pintype "passive"))
    )
    (net (code "57") (name "SWDIO") (class "Default")
      (node (ref "IC1") (pin "23") (pinfunction "PA13_23") (pintype "bidirectional"))
      (node (ref "R7") (pin "1") (pinfunction "1_1") (pintype "passive"))
    )
    (net (code "58") (name "unconnected-(IC1-PA10-Pad20)") (class "Default")
      (node (ref "IC1") (pin "20") (pinfunction "PA10_20") (pintype "bidirectional"))
    )
    (net (code "59") (name "unconnected-(IC1-PG10-NRST-Pad4)") (class "Default")
      (node (ref "IC1") (pin "4") (pinfunction "PG10-NRST_4") (pintype "bidirectional"))
    )
    (net (code "60") (name "unconnected-(U2-ADJ{slash}NC-Pad3)") (class "Default")
      (node (ref "U2") (pin "3") (pinfunction "ADJ/NC_3") (pintype "passive"))
    )
  )
)
